# mcu-breather.net
KiCad netlist of a schematic drawn in Altium Designer
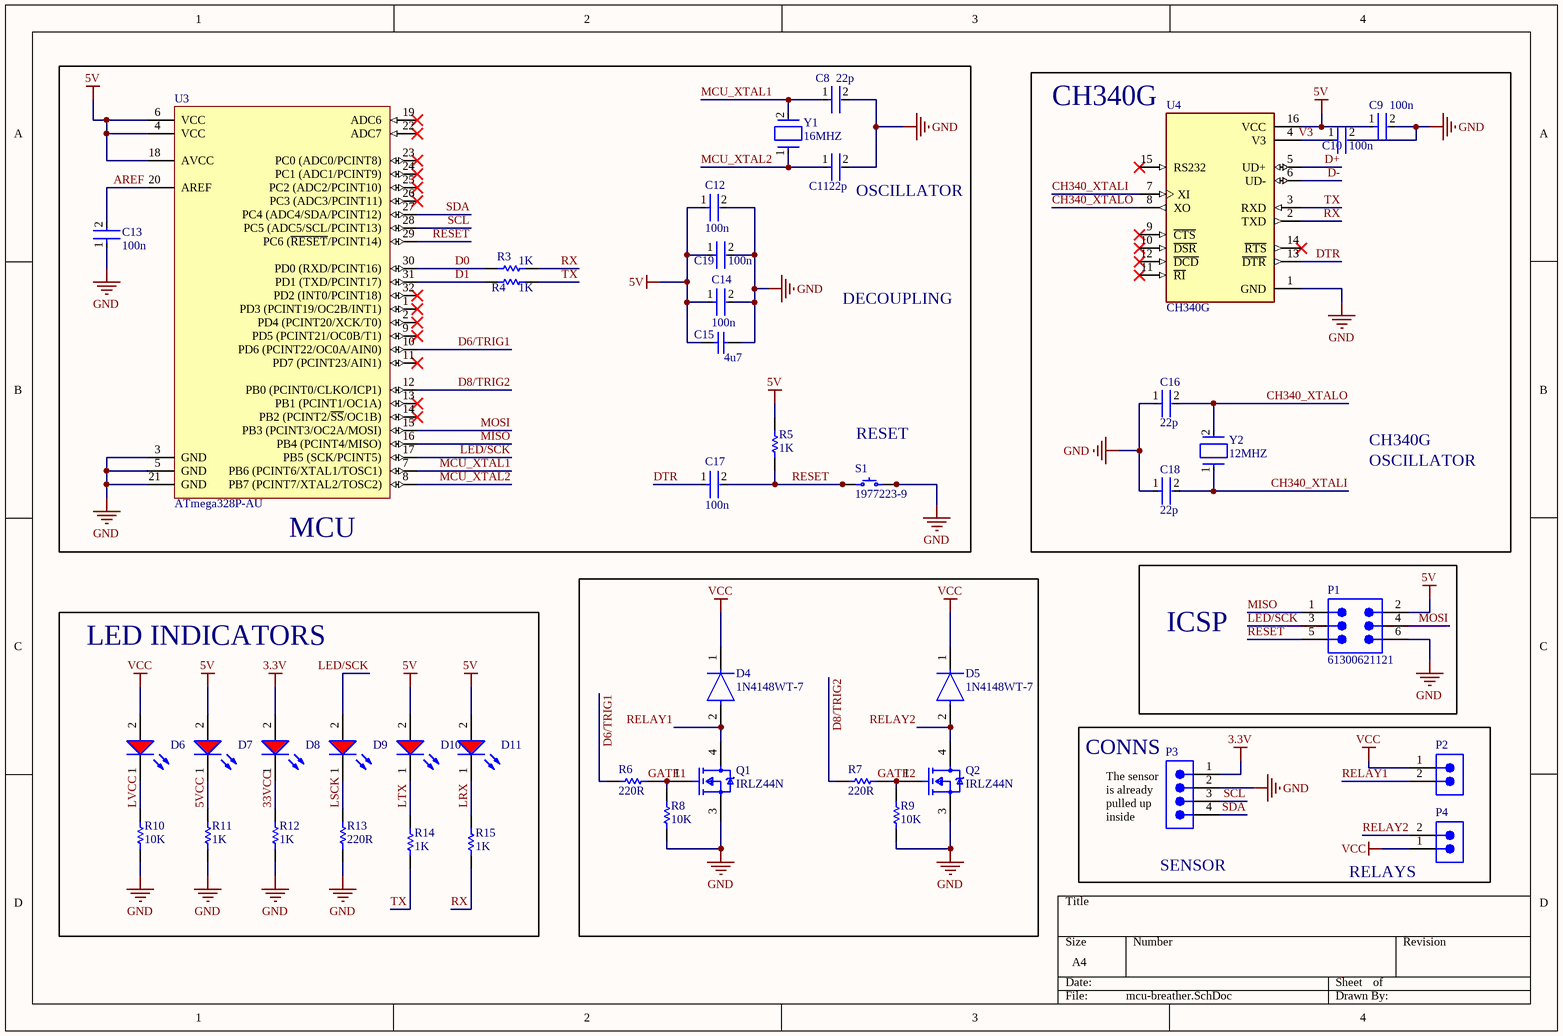
[diagram p0: mcu-breather.SchDoc]

(export (version "E")
  (design (tool "Eeschema 10.0.6"))
  (components
    (comp (ref "C8")
      (value "22p")
      (footprint "FP-GRM188-0_1-e0_2_0_55-IPC_A")
      (description "Chip Multilayer Ceramic Capacitors for General Purpose, 0603, 10uF, X5R, 15%, 20%, 6.3V")
      (fields (field (name "VOLTAGE") "6.3V") (field (name "TOLERANCE") "20%"))
      (libsource (lib "Altium Content Vault") (part "02cd4be3c70576c341d710602a673aa"))
    )
    (comp (ref "C9")
      (value "100n")
      (footprint "FP-GRM188-0_1-e0_2_0_55-IPC_A")
      (description "Chip Multilayer Ceramic Capacitors for General Purpose, 0603, 10uF, X5R, 15%, 20%, 6.3V")
      (fields (field (name "VOLTAGE") "6.3V") (field (name "TOLERANCE") "20%"))
      (libsource (lib "Altium Content Vault") (part "02cd4be3c70576c341d710602a673aa"))
    )
    (comp (ref "C10")
      (value "100n")
      (footprint "FP-GRM188-0_1-e0_2_0_55-IPC_A")
      (description "Chip Multilayer Ceramic Capacitors for General Purpose, 0603, 10uF, X5R, 15%, 20%, 6.3V")
      (fields (field (name "VOLTAGE") "6.3V") (field (name "TOLERANCE") "20%"))
      (libsource (lib "Altium Content Vault") (part "02cd4be3c70576c341d710602a673aa"))
    )
    (comp (ref "C11")
      (value "22p")
      (footprint "FP-GRM188-0_1-e0_2_0_55-IPC_A")
      (description "Chip Multilayer Ceramic Capacitors for General Purpose, 0603, 10uF, X5R, 15%, 20%, 6.3V")
      (fields (field (name "VOLTAGE") "6.3V") (field (name "TOLERANCE") "20%"))
      (libsource (lib "Altium Content Vault") (part "02cd4be3c70576c341d710602a673aa"))
    )
    (comp (ref "C12")
      (value "100n")
      (footprint "FP-GRM188-0_1-e0_2_0_55-IPC_A")
      (description "Chip Multilayer Ceramic Capacitors for General Purpose, 0603, 10uF, X5R, 15%, 20%, 6.3V")
      (fields (field (name "VOLTAGE") "6.3V") (field (name "TOLERANCE") "20%"))
      (libsource (lib "Altium Content Vault") (part "02cd4be3c70576c341d710602a673aa"))
    )
    (comp (ref "C13")
      (value "100n")
      (footprint "FP-GRM188-0_1-e0_2_0_55-IPC_A")
      (description "Chip Multilayer Ceramic Capacitors for General Purpose, 0603, 10uF, X5R, 15%, 20%, 6.3V")
      (fields (field (name "VOLTAGE") "6.3V") (field (name "TOLERANCE") "20%"))
      (libsource (lib "Altium Content Vault") (part "02cd4be3c70576c341d710602a673aa"))
    )
    (comp (ref "C14")
      (value "100n")
      (footprint "FP-GRM188-0_1-e0_2_0_55-IPC_A")
      (description "Chip Multilayer Ceramic Capacitors for General Purpose, 0603, 10uF, X5R, 15%, 20%, 6.3V")
      (fields (field (name "VOLTAGE") "6.3V") (field (name "TOLERANCE") "20%"))
      (libsource (lib "Altium Content Vault") (part "02cd4be3c70576c341d710602a673aa"))
    )
    (comp (ref "C15")
      (value "4u7")
      (footprint "CAPC2013X135X45NL10T25")
      (fields (field (name "MANUFACTURER") "Murata") (field (name "PART NUMBER") "GRM21BR72E103KW03L"))
      (libsource (lib "Altium Content Vault") (part "CAP"))
    )
    (comp (ref "C16")
      (value "22p")
      (footprint "FP-GRM188-0_1-e0_2_0_55-IPC_A")
      (description "Chip Multilayer Ceramic Capacitors for General Purpose, 0603, 10uF, X5R, 15%, 20%, 6.3V")
      (fields (field (name "VOLTAGE") "6.3V") (field (name "TOLERANCE") "20%"))
      (libsource (lib "Altium Content Vault") (part "02cd4be3c70576c341d710602a673aa"))
    )
    (comp (ref "C17")
      (value "100n")
      (footprint "FP-GRM188-0_1-e0_2_0_55-IPC_A")
      (description "Chip Multilayer Ceramic Capacitors for General Purpose, 0603, 10uF, X5R, 15%, 20%, 6.3V")
      (fields (field (name "VOLTAGE") "6.3V") (field (name "TOLERANCE") "20%"))
      (libsource (lib "Altium Content Vault") (part "02cd4be3c70576c341d710602a673aa"))
    )
    (comp (ref "C18")
      (value "22p")
      (footprint "FP-GRM188-0_1-e0_2_0_55-IPC_A")
      (description "Chip Multilayer Ceramic Capacitors for General Purpose, 0603, 10uF, X5R, 15%, 20%, 6.3V")
      (fields (field (name "VOLTAGE") "6.3V") (field (name "TOLERANCE") "20%"))
      (libsource (lib "Altium Content Vault") (part "02cd4be3c70576c341d710602a673aa"))
    )
    (comp (ref "C19")
      (value "100n")
      (footprint "FP-GRM188-0_1-e0_2_0_55-IPC_A")
      (description "Chip Multilayer Ceramic Capacitors for General Purpose, 0603, 10uF, X5R, 15%, 20%, 6.3V")
      (fields (field (name "VOLTAGE") "6.3V") (field (name "TOLERANCE") "20%"))
      (libsource (lib "Altium Content Vault") (part "02cd4be3c70576c341d710602a673aa"))
    )
    (comp (ref "D4")
      (value "1N4148WT-7")
      (footprint "FP-SOD523-MFG")
      (description "DIODE GEN PURP 80V 125MA SOD523")
      (libsource (lib "Altium Content Vault") (part "d7152d700b627762746794eb795d46e"))
    )
    (comp (ref "D5")
      (value "1N4148WT-7")
      (footprint "FP-SOD523-MFG")
      (description "DIODE GEN PURP 80V 125MA SOD523")
      (libsource (lib "Altium Content Vault") (part "d7152d700b627762746794eb795d46e"))
    )
    (comp (ref "D6")
      (value "150080RS75000")
      (footprint "WL-SMCW_0805_150080xx75000")
      (libsource (lib "Altium Content Vault") (part "LED_Red_2A-1K"))
    )
    (comp (ref "D7")
      (value "150080RS75000")
      (footprint "WL-SMCW_0805_150080xx75000")
      (libsource (lib "Altium Content Vault") (part "LED_Red_2A-1K"))
    )
    (comp (ref "D8")
      (value "150080RS75000")
      (footprint "WL-SMCW_0805_150080xx75000")
      (libsource (lib "Altium Content Vault") (part "LED_Red_2A-1K"))
    )
    (comp (ref "D9")
      (value "150080RS75000")
      (footprint "WL-SMCW_0805_150080xx75000")
      (libsource (lib "Altium Content Vault") (part "LED_Red_2A-1K"))
    )
    (comp (ref "D10")
      (value "150080RS75000")
      (footprint "WL-SMCW_0805_150080xx75000")
      (libsource (lib "Altium Content Vault") (part "LED_Red_2A-1K"))
    )
    (comp (ref "D11")
      (value "150080RS75000")
      (footprint "WL-SMCW_0805_150080xx75000")
      (libsource (lib "Altium Content Vault") (part "LED_Red_2A-1K"))
    )
    (comp (ref "P1")
      (value "61300621121")
      (footprint "61300621121")
      (libsource (lib "Altium Content Vault") (part "Header_Male_2R_06P"))
    )
    (comp (ref "P2")
      (value "691311500002")
      (footprint "691311500002")
      (fields (field (name "VOLTAGE") "300V"))
      (libsource (lib "") (part "TBL - 1R - 02P - Male_1"))
    )
    (comp (ref "P3")
      (value "691311500104")
      (footprint "691311500104")
      (fields (field (name "VOLTAGE") "300V"))
      (libsource (lib "Altium Content Vault") (part "TBL - 1R - 04P - Male"))
    )
    (comp (ref "P4")
      (value "691311500002")
      (footprint "691311500002")
      (fields (field (name "VOLTAGE") "300V"))
      (libsource (lib "Altium Content Vault") (part "TBL - 1R - 02P - Male"))
    )
    (comp (ref "Q1")
      (value "IRLZ44N")
      (footprint "FP-PG-TO263-3-MFG")
      (description "MOSFET N-CH 55V 47A D2PAK - IRLZ44NSTRLPBF")
      (libsource (lib "Altium Content Vault") (part "cdf1c68f84cb049e5ebc85739c3fcf6"))
    )
    (comp (ref "Q2")
      (value "IRLZ44N")
      (footprint "FP-PG-TO263-3-MFG")
      (description "MOSFET N-CH 55V 47A D2PAK - IRLZ44NSTRLPBF")
      (libsource (lib "Altium Content Vault") (part "cdf1c68f84cb049e5ebc85739c3fcf6"))
    )
    (comp (ref "R3")
      (value "1K")
      (footprint "RESC2013X60X35ML10T20")
      (description "Chip Resistor, 1 KOhm, +/- 1%, 125 mW, -55 to 155 degC, 0805 (2012 Metric), RoHS, Tape and Reel")
      (fields (field (name "TOLERANCE") "1%") (field (name "MANUFACTURER") "Yageo"))
      (libsource (lib "Altium Content Vault") (part "RES-2"))
    )
    (comp (ref "R4")
      (value "1K")
      (footprint "RESC2013X60X35ML10T20")
      (description "Chip Resistor, 1 KOhm, +/- 1%, 125 mW, -55 to 155 degC, 0805 (2012 Metric), RoHS, Tape and Reel")
      (fields (field (name "TOLERANCE") "1%") (field (name "MANUFACTURER") "Yageo"))
      (libsource (lib "Altium Content Vault") (part "RES-2"))
    )
    (comp (ref "R5")
      (value "1K")
      (footprint "RESC2013X60X35ML10T20")
      (description "Chip Resistor, 1 KOhm, +/- 1%, 125 mW, -55 to 155 degC, 0805 (2012 Metric), RoHS, Tape and Reel")
      (fields (field (name "TOLERANCE") "1%") (field (name "MANUFACTURER") "Yageo"))
      (libsource (lib "Altium Content Vault") (part "RES-2"))
    )
    (comp (ref "R6")
      (value "220R")
      (footprint "RESC2013X60X35ML10T20")
      (description "Chip Resistor, 1 KOhm, +/- 1%, 125 mW, -55 to 155 degC, 0805 (2012 Metric), RoHS, Tape and Reel")
      (fields (field (name "TOLERANCE") "1%") (field (name "MANUFACTURER") "Yageo"))
      (libsource (lib "Altium Content Vault") (part "RES-2"))
    )
    (comp (ref "R7")
      (value "220R")
      (footprint "RESC2013X60X35ML10T20")
      (description "Chip Resistor, 1 KOhm, +/- 1%, 125 mW, -55 to 155 degC, 0805 (2012 Metric), RoHS, Tape and Reel")
      (fields (field (name "TOLERANCE") "1%") (field (name "MANUFACTURER") "Yageo"))
      (libsource (lib "Altium Content Vault") (part "RES-2"))
    )
    (comp (ref "R8")
      (value "10K")
      (footprint "RESC2013X60X35ML10T20")
      (description "Chip Resistor, 1 KOhm, +/- 1%, 125 mW, -55 to 155 degC, 0805 (2012 Metric), RoHS, Tape and Reel")
      (fields (field (name "TOLERANCE") "1%") (field (name "MANUFACTURER") "Yageo"))
      (libsource (lib "Altium Content Vault") (part "RES-2"))
    )
    (comp (ref "R9")
      (value "10K")
      (footprint "RESC2013X60X35ML10T20")
      (description "Chip Resistor, 1 KOhm, +/- 1%, 125 mW, -55 to 155 degC, 0805 (2012 Metric), RoHS, Tape and Reel")
      (fields (field (name "TOLERANCE") "1%") (field (name "MANUFACTURER") "Yageo"))
      (libsource (lib "Altium Content Vault") (part "RES-2"))
    )
    (comp (ref "R10")
      (value "10K")
      (footprint "RESC2013X60X35ML10T20")
      (description "Chip Resistor, 1 KOhm, +/- 1%, 125 mW, -55 to 155 degC, 0805 (2012 Metric), RoHS, Tape and Reel")
      (fields (field (name "TOLERANCE") "1%") (field (name "MANUFACTURER") "Yageo"))
      (libsource (lib "Altium Content Vault") (part "RES-2"))
    )
    (comp (ref "R11")
      (value "1K")
      (footprint "RESC2013X60X35ML10T20")
      (description "Chip Resistor, 1 KOhm, +/- 1%, 125 mW, -55 to 155 degC, 0805 (2012 Metric), RoHS, Tape and Reel")
      (fields (field (name "TOLERANCE") "1%") (field (name "MANUFACTURER") "Yageo"))
      (libsource (lib "Altium Content Vault") (part "RES-2"))
    )
    (comp (ref "R12")
      (value "1K")
      (footprint "RESC2013X60X35ML10T20")
      (description "Chip Resistor, 1 KOhm, +/- 1%, 125 mW, -55 to 155 degC, 0805 (2012 Metric), RoHS, Tape and Reel")
      (fields (field (name "TOLERANCE") "1%") (field (name "MANUFACTURER") "Yageo"))
      (libsource (lib "Altium Content Vault") (part "RES-2"))
    )
    (comp (ref "R13")
      (value "220R")
      (footprint "RESC2013X60X35ML10T20")
      (description "Chip Resistor, 1 KOhm, +/- 1%, 125 mW, -55 to 155 degC, 0805 (2012 Metric), RoHS, Tape and Reel")
      (fields (field (name "TOLERANCE") "1%") (field (name "MANUFACTURER") "Yageo"))
      (libsource (lib "Altium Content Vault") (part "RES-2"))
    )
    (comp (ref "R14")
      (value "1K")
      (footprint "RESC2013X60X35ML10T20")
      (description "Chip Resistor, 1 KOhm, +/- 1%, 125 mW, -55 to 155 degC, 0805 (2012 Metric), RoHS, Tape and Reel")
      (fields (field (name "TOLERANCE") "1%") (field (name "MANUFACTURER") "Yageo"))
      (libsource (lib "Altium Content Vault") (part "RES-2"))
    )
    (comp (ref "R15")
      (value "1K")
      (footprint "RESC2013X60X35ML10T20")
      (description "Chip Resistor, 1 KOhm, +/- 1%, 125 mW, -55 to 155 degC, 0805 (2012 Metric), RoHS, Tape and Reel")
      (fields (field (name "TOLERANCE") "1%") (field (name "MANUFACTURER") "Yageo"))
      (libsource (lib "Altium Content Vault") (part "RES-2"))
    )
    (comp (ref "S1")
      (value "1977223-9")
      (footprint "TE FSM4JSMA")
      (description "SWITCH TACTILE SPST-NO 0.05A 24V")
      (fields (field (name "MANUFACTURER") "TE Connectivity ALCOSWITCH Switches"))
      (libsource (lib "Celestial Altium Library - altium_library") (part "SPST-NO 4 PIN"))
    )
    (comp (ref "U3")
      (value "ATmega328P-AU")
      (footprint "32A_M")
      (libsource (lib "Altium Content Vault") (part "MC-8B-ATM48-SQ32"))
    )
    (comp (ref "U4")
      (value "CH340G")
      (footprint "SOIC127P600X180-16N")
      (description "USB Interface Integrated Circuit")
      (fields (field (name "MP") "Ch340G") (field (name "MF") "WCH"))
      (libsource (lib "CH340G (1)") (part "CH340G"))
    )
    (comp (ref "Y1")
      (value "16MHZ")
      (footprint "FP-ABM7-MFG")
      (description "Crystal 16MHz ±20ppm 18pF SMD-2 6mm x 3.5mm - ABM7-16.000MHZ-D2Y-T")
      (fields (field (name "TOLERANCE") "20ppm"))
      (libsource (lib "Altium Content Vault") (part "c23a69dc6c9e2f18f2079038eb95dd1"))
    )
    (comp (ref "Y2")
      (value "12MHZ")
      (footprint "FP-ABM7-MFG")
      (description "Crystal 12MHz ±20ppm 18pF SMD-2 6mm x 3.5mm - ABM7-12.000MHZ-D2Y-T")
      (fields (field (name "TOLERANCE") "20ppm"))
      (libsource (lib "Altium Content Vault") (part "c23a69dc6c9e2f18f2079038eb95dd1"))
    )
  )
  (nets
    (net (code "1") (name "/5VCC") (class "Default")
      (node (ref "D7") (pin "1") (pinfunction "K_1") (pintype "passive"))
      (node (ref "R11") (pin "2") (pinfunction "2_2") (pintype "passive"))
    )
    (net (code "2") (name "/33VCC") (class "Default")
      (node (ref "D8") (pin "1") (pinfunction "K_1") (pintype "passive"))
      (node (ref "R12") (pin "2") (pinfunction "2_2") (pintype "passive"))
    )
    (net (code "3") (name "/AREF") (class "Default")
      (node (ref "C13") (pin "2") (pinfunction "2_2") (pintype "passive"))
      (node (ref "U3") (pin "20") (pinfunction "AREF_20") (pintype "passive"))
    )
    (net (code "4") (name "/CH340_XTALI") (class "Default")
      (node (ref "C18") (pin "2") (pinfunction "2_2") (pintype "passive"))
      (node (ref "U4") (pin "7") (pinfunction "XI_7") (pintype "input"))
      (node (ref "Y2") (pin "1") (pinfunction "1_1") (pintype "passive"))
    )
    (net (code "5") (name "/CH340_XTALO") (class "Default")
      (node (ref "C16") (pin "2") (pinfunction "2_2") (pintype "passive"))
      (node (ref "U4") (pin "8") (pinfunction "XO_8") (pintype "output"))
      (node (ref "Y2") (pin "2") (pinfunction "2_2") (pintype "passive"))
    )
    (net (code "6") (name "/D+") (class "Default")
      (node (ref "U4") (pin "5") (pinfunction "UD+_5") (pintype "bidirectional"))
    )
    (net (code "7") (name "/D-") (class "Default")
      (node (ref "U4") (pin "6") (pinfunction "UD-_6") (pintype "bidirectional"))
    )
    (net (code "8") (name "/D0") (class "Default")
      (node (ref "R3") (pin "1") (pinfunction "1_1") (pintype "passive"))
      (node (ref "U3") (pin "30") (pinfunction "PD0_(RXD/PCINT16)_30") (pintype "bidirectional"))
    )
    (net (code "9") (name "/D1") (class "Default")
      (node (ref "R4") (pin "1") (pinfunction "1_1") (pintype "passive"))
      (node (ref "U3") (pin "31") (pinfunction "PD1_(TXD/PCINT17)_31") (pintype "bidirectional"))
    )
    (net (code "10") (name "/D6{slash}TRIG1") (class "Default")
      (node (ref "R6") (pin "2") (pinfunction "2_2") (pintype "passive"))
      (node (ref "U3") (pin "10") (pinfunction "PD6_(PCINT22/OC0A/AIN0)_10") (pintype "bidirectional"))
    )
    (net (code "11") (name "/D8{slash}TRIG2") (class "Default")
      (node (ref "R7") (pin "2") (pinfunction "2_2") (pintype "passive"))
      (node (ref "U3") (pin "12") (pinfunction "PB0_(PCINT0/CLKO/ICP1)_12") (pintype "bidirectional"))
    )
    (net (code "12") (name "/DTR") (class "Default")
      (node (ref "C17") (pin "1") (pinfunction "1_1") (pintype "passive"))
      (node (ref "U4") (pin "13") (pinfunction "~{DTR}_13") (pintype "output"))
    )
    (net (code "15") (name "/LED{slash}SCK") (class "Default")
      (node (ref "D9") (pin "2") (pinfunction "A_2") (pintype "passive"))
      (node (ref "P1") (pin "3") (pinfunction "3_3") (pintype "passive"))
      (node (ref "U3") (pin "17") (pinfunction "PB5_(SCK/PCINT5)_17") (pintype "bidirectional"))
    )
    (net (code "16") (name "/LRX") (class "Default")
      (node (ref "D11") (pin "1") (pinfunction "K_1") (pintype "passive"))
      (node (ref "R15") (pin "2") (pinfunction "2_2") (pintype "passive"))
    )
    (net (code "17") (name "/LSCK") (class "Default")
      (node (ref "D9") (pin "1") (pinfunction "K_1") (pintype "passive"))
      (node (ref "R13") (pin "1") (pinfunction "1_1") (pintype "passive"))
    )
    (net (code "18") (name "/LTX") (class "Default")
      (node (ref "D10") (pin "1") (pinfunction "K_1") (pintype "passive"))
      (node (ref "R14") (pin "2") (pinfunction "2_2") (pintype "passive"))
    )
    (net (code "19") (name "/LVCC") (class "Default")
      (node (ref "D6") (pin "1") (pinfunction "K_1") (pintype "passive"))
      (node (ref "R10") (pin "1") (pinfunction "1_1") (pintype "passive"))
    )
    (net (code "20") (name "/MCU_XTAL1") (class "Default")
      (node (ref "C8") (pin "1") (pinfunction "1_1") (pintype "passive"))
      (node (ref "U3") (pin "7") (pinfunction "PB6_(PCINT6/XTAL1/TOSC1)_7") (pintype "bidirectional"))
      (node (ref "Y1") (pin "2") (pinfunction "2_2") (pintype "passive"))
    )
    (net (code "21") (name "/MCU_XTAL2") (class "Default")
      (node (ref "C11") (pin "1") (pinfunction "1_1") (pintype "passive"))
      (node (ref "U3") (pin "8") (pinfunction "PB7_(PCINT7/XTAL2/TOSC2)_8") (pintype "bidirectional"))
      (node (ref "Y1") (pin "1") (pinfunction "1_1") (pintype "passive"))
    )
    (net (code "22") (name "/MISO") (class "Default")
      (node (ref "P1") (pin "1") (pinfunction "1_1") (pintype "passive"))
      (node (ref "U3") (pin "16") (pinfunction "PB4_(PCINT4/MISO)_16") (pintype "bidirectional"))
    )
    (net (code "23") (name "/MOSI") (class "Default")
      (node (ref "P1") (pin "4") (pinfunction "4_4") (pintype "passive"))
      (node (ref "U3") (pin "15") (pinfunction "PB3_(PCINT3/OC2A/MOSI)_15") (pintype "bidirectional"))
    )
    (net (code "24") (name "/RELAY1") (class "Default")
      (node (ref "D4") (pin "2") (pinfunction "A_2") (pintype "passive"))
      (node (ref "P2") (pin "2") (pinfunction "2_2") (pintype "passive"))
      (node (ref "Q1") (pin "4") (pinfunction "D_4") (pintype "passive"))
    )
    (net (code "25") (name "/RELAY2") (class "Default")
      (node (ref "D5") (pin "2") (pinfunction "A_2") (pintype "passive"))
      (node (ref "P4") (pin "2") (pinfunction "2_2") (pintype "passive"))
      (node (ref "Q2") (pin "4") (pinfunction "D_4") (pintype "passive"))
    )
    (net (code "26") (name "/RESET") (class "Default")
      (node (ref "C17") (pin "2") (pinfunction "2_2") (pintype "passive"))
      (node (ref "P1") (pin "5") (pinfunction "5_5") (pintype "passive"))
      (node (ref "R5") (pin "1") (pinfunction "1_1") (pintype "passive"))
      (node (ref "S1") (pin "1") (pinfunction "1_1") (pintype "passive"))
      (node (ref "S1") (pin "2") (pinfunction "2_2") (pintype "passive"))
      (node (ref "U3") (pin "29") (pinfunction "PC6_(~{RESET}/PCINT14)_29") (pintype "bidirectional"))
    )
    (net (code "27") (name "/RX") (class "Default")
      (node (ref "R15") (pin "1") (pinfunction "1_1") (pintype "passive"))
      (node (ref "R3") (pin "2") (pinfunction "2_2") (pintype "passive"))
      (node (ref "U4") (pin "2") (pinfunction "TXD_2") (pintype "output"))
    )
    (net (code "28") (name "/SCL") (class "Default")
      (node (ref "P3") (pin "3") (pinfunction "3_3") (pintype "passive"))
      (node (ref "U3") (pin "28") (pinfunction "PC5_(ADC5/SCL/PCINT13)_28") (pintype "bidirectional"))
    )
    (net (code "29") (name "/SDA") (class "Default")
      (node (ref "P3") (pin "4") (pinfunction "4_4") (pintype "passive"))
      (node (ref "U3") (pin "27") (pinfunction "PC4_(ADC4/SDA/PCINT12)_27") (pintype "bidirectional"))
    )
    (net (code "30") (name "/TX") (class "Default")
      (node (ref "R14") (pin "1") (pinfunction "1_1") (pintype "passive"))
      (node (ref "R4") (pin "2") (pinfunction "2_2") (pintype "passive"))
      (node (ref "U4") (pin "3") (pinfunction "RXD_3") (pintype "input"))
    )
    (net (code "31") (name "/V3") (class "Default")
      (node (ref "C10") (pin "1") (pinfunction "1_1") (pintype "passive"))
      (node (ref "U4") (pin "4") (pinfunction "V3_4") (pintype "power_in"))
    )
    (net (code "32") (name "3.3V") (class "Default")
      (node (ref "D8") (pin "2") (pinfunction "A_2") (pintype "passive"))
      (node (ref "P3") (pin "1") (pinfunction "1_1") (pintype "passive"))
    )
    (net (code "33") (name "5V") (class "Default")
      (node (ref "C12") (pin "1") (pinfunction "1_1") (pintype "passive"))
      (node (ref "C14") (pin "1") (pinfunction "1_1") (pintype "passive"))
      (node (ref "C15") (pin "1") (pinfunction "1_1") (pintype "passive"))
      (node (ref "C19") (pin "1") (pinfunction "1_1") (pintype "passive"))
      (node (ref "C9") (pin "1") (pinfunction "1_1") (pintype "passive"))
      (node (ref "D10") (pin "2") (pinfunction "A_2") (pintype "passive"))
      (node (ref "D11") (pin "2") (pinfunction "A_2") (pintype "passive"))
      (node (ref "D7") (pin "2") (pinfunction "A_2") (pintype "passive"))
      (node (ref "P1") (pin "2") (pinfunction "2_2") (pintype "passive"))
      (node (ref "R5") (pin "2") (pinfunction "2_2") (pintype "passive"))
      (node (ref "U3") (pin "18") (pinfunction "AVCC_18") (pintype "power_in"))
      (node (ref "U3") (pin "4") (pinfunction "VCC_4") (pintype "power_in"))
      (node (ref "U3") (pin "6") (pinfunction "VCC_6") (pintype "power_in"))
      (node (ref "U4") (pin "16") (pinfunction "VCC_16") (pintype "power_in"))
    )
    (net (code "34") (name "GND") (class "Default")
      (node (ref "C10") (pin "2") (pinfunction "2_2") (pintype "passive"))
      (node (ref "C11") (pin "2") (pinfunction "2_2") (pintype "passive"))
      (node (ref "C12") (pin "2") (pinfunction "2_2") (pintype "passive"))
      (node (ref "C13") (pin "1") (pinfunction "1_1") (pintype "passive"))
      (node (ref "C14") (pin "2") (pinfunction "2_2") (pintype "passive"))
      (node (ref "C15") (pin "2") (pinfunction "2_2") (pintype "passive"))
      (node (ref "C16") (pin "1") (pinfunction "1_1") (pintype "passive"))
      (node (ref "C18") (pin "1") (pinfunction "1_1") (pintype "passive"))
      (node (ref "C19") (pin "2") (pinfunction "2_2") (pintype "passive"))
      (node (ref "C8") (pin "2") (pinfunction "2_2") (pintype "passive"))
      (node (ref "C9") (pin "2") (pinfunction "2_2") (pintype "passive"))
      (node (ref "P1") (pin "6") (pinfunction "6_6") (pintype "passive"))
      (node (ref "P3") (pin "2") (pinfunction "2_2") (pintype "passive"))
      (node (ref "Q1") (pin "3") (pinfunction "S_3") (pintype "passive"))
      (node (ref "Q2") (pin "3") (pinfunction "S_3") (pintype "passive"))
      (node (ref "R10") (pin "2") (pinfunction "2_2") (pintype "passive"))
      (node (ref "R11") (pin "1") (pinfunction "1_1") (pintype "passive"))
      (node (ref "R12") (pin "1") (pinfunction "1_1") (pintype "passive"))
      (node (ref "R13") (pin "2") (pinfunction "2_2") (pintype "passive"))
      (node (ref "R8") (pin "2") (pinfunction "2_2") (pintype "passive"))
      (node (ref "R9") (pin "2") (pinfunction "2_2") (pintype "passive"))
      (node (ref "S1") (pin "3") (pinfunction "3_3") (pintype "passive"))
      (node (ref "S1") (pin "4") (pinfunction "4_4") (pintype "passive"))
      (node (ref "U3") (pin "21") (pinfunction "GND_21") (pintype "power_in"))
      (node (ref "U3") (pin "3") (pinfunction "GND_3") (pintype "power_in"))
      (node (ref "U3") (pin "5") (pinfunction "GND_5") (pintype "power_in"))
      (node (ref "U4") (pin "1") (pinfunction "GND_1") (pintype "power_in"))
    )
    (net (code "35") (name "Net-(Q1-G)") (class "Default")
      (node (ref "Q1") (pin "1") (pinfunction "G_1") (pintype "passive"))
      (node (ref "R6") (pin "1") (pinfunction "1_1") (pintype "passive"))
      (node (ref "R8") (pin "1") (pinfunction "1_1") (pintype "passive"))
    )
    (net (code "36") (name "Net-(Q2-G)") (class "Default")
      (node (ref "Q2") (pin "1") (pinfunction "G_1") (pintype "passive"))
      (node (ref "R7") (pin "1") (pinfunction "1_1") (pintype "passive"))
      (node (ref "R9") (pin "1") (pinfunction "1_1") (pintype "passive"))
    )
    (net (code "37") (name "VCC") (class "Default")
      (node (ref "D4") (pin "1") (pinfunction "C_1") (pintype "passive"))
      (node (ref "D5") (pin "1") (pinfunction "C_1") (pintype "passive"))
      (node (ref "D6") (pin "2") (pinfunction "A_2") (pintype "passive"))
      (node (ref "P2") (pin "1") (pinfunction "1_1") (pintype "passive"))
      (node (ref "P4") (pin "1") (pinfunction "1_1") (pintype "passive"))
    )
    (net (code "38") (name "unconnected-(U3-ADC6-Pad19)") (class "Default")
      (node (ref "U3") (pin "19") (pinfunction "ADC6_19") (pintype "input+no_connect"))
    )
    (net (code "39") (name "unconnected-(U3-ADC7-Pad22)") (class "Default")
      (node (ref "U3") (pin "22") (pinfunction "ADC7_22") (pintype "input+no_connect"))
    )
    (net (code "40") (name "unconnected-(U3-PB1_(PCINT1{slash}OC1A)-Pad13)") (class "Default")
      (node (ref "U3") (pin "13") (pinfunction "PB1_(PCINT1/OC1A)_13") (pintype "bidirectional+no_connect"))
    )
    (net (code "41") (name "unconnected-(U3-PB2_(PCINT2{slash}~{SS}{slash}OC1B)-Pad14)") (class "Default")
      (node (ref "U3") (pin "14") (pinfunction "PB2_(PCINT2/~{SS}/OC1B)_14") (pintype "bidirectional+no_connect"))
    )
    (net (code "42") (name "unconnected-(U3-PC0_(ADC0{slash}PCINT8)-Pad23)") (class "Default")
      (node (ref "U3") (pin "23") (pinfunction "PC0_(ADC0/PCINT8)_23") (pintype "bidirectional+no_connect"))
    )
    (net (code "43") (name "unconnected-(U3-PC1_(ADC1{slash}PCINT9)-Pad24)") (class "Default")
      (node (ref "U3") (pin "24") (pinfunction "PC1_(ADC1/PCINT9)_24") (pintype "bidirectional+no_connect"))
    )
    (net (code "44") (name "unconnected-(U3-PC2_(ADC2{slash}PCINT10)-Pad25)") (class "Default")
      (node (ref "U3") (pin "25") (pinfunction "PC2_(ADC2/PCINT10)_25") (pintype "bidirectional+no_connect"))
    )
    (net (code "45") (name "unconnected-(U3-PC3_(ADC3{slash}PCINT11)-Pad26)") (class "Default")
      (node (ref "U3") (pin "26") (pinfunction "PC3_(ADC3/PCINT11)_26") (pintype "bidirectional+no_connect"))
    )
    (net (code "46") (name "unconnected-(U3-PD2_(INT0{slash}PCINT18)-Pad32)") (class "Default")
      (node (ref "U3") (pin "32") (pinfunction "PD2_(INT0/PCINT18)_32") (pintype "bidirectional+no_connect"))
    )
    (net (code "47") (name "unconnected-(U3-PD3_(PCINT19{slash}OC2B{slash}INT1)-Pad1)") (class "Default")
      (node (ref "U3") (pin "1") (pinfunction "PD3_(PCINT19/OC2B/INT1)_1") (pintype "bidirectional+no_connect"))
    )
    (net (code "48") (name "unconnected-(U3-PD4_(PCINT20{slash}XCK{slash}T0)-Pad2)") (class "Default")
      (node (ref "U3") (pin "2") (pinfunction "PD4_(PCINT20/XCK/T0)_2") (pintype "bidirectional+no_connect"))
    )
    (net (code "49") (name "unconnected-(U3-PD5_(PCINT21{slash}OC0B{slash}T1)-Pad9)") (class "Default")
      (node (ref "U3") (pin "9") (pinfunction "PD5_(PCINT21/OC0B/T1)_9") (pintype "bidirectional+no_connect"))
    )
    (net (code "50") (name "unconnected-(U3-PD7_(PCINT23{slash}AIN1)-Pad11)") (class "Default")
      (node (ref "U3") (pin "11") (pinfunction "PD7_(PCINT23/AIN1)_11") (pintype "bidirectional+no_connect"))
    )
    (net (code "51") (name "unconnected-(U4-RS232-Pad15)") (class "Default")
      (node (ref "U4") (pin "15") (pinfunction "RS232_15") (pintype "input+no_connect"))
    )
    (net (code "52") (name "unconnected-(U4-~{CTS}-Pad9)") (class "Default")
      (node (ref "U4") (pin "9") (pinfunction "~{CTS}_9") (pintype "input+no_connect"))
    )
    (net (code "53") (name "unconnected-(U4-~{DCD}-Pad12)") (class "Default")
      (node (ref "U4") (pin "12") (pinfunction "~{DCD}_12") (pintype "input+no_connect"))
    )
    (net (code "54") (name "unconnected-(U4-~{DSR}-Pad10)") (class "Default")
      (node (ref "U4") (pin "10") (pinfunction "~{DSR}_10") (pintype "input+no_connect"))
    )
    (net (code "55") (name "unconnected-(U4-~{RI}-Pad11)") (class "Default")
      (node (ref "U4") (pin "11") (pinfunction "~{RI}_11") (pintype "input+no_connect"))
    )
    (net (code "56") (name "unconnected-(U4-~{RTS}-Pad14)") (class "Default")
      (node (ref "U4") (pin "14") (pinfunction "~{RTS}_14") (pintype "output+no_connect"))
    )
  )
)
